# BatteryProtection.net
KiCad netlist of a schematic drawn in Altium Designer
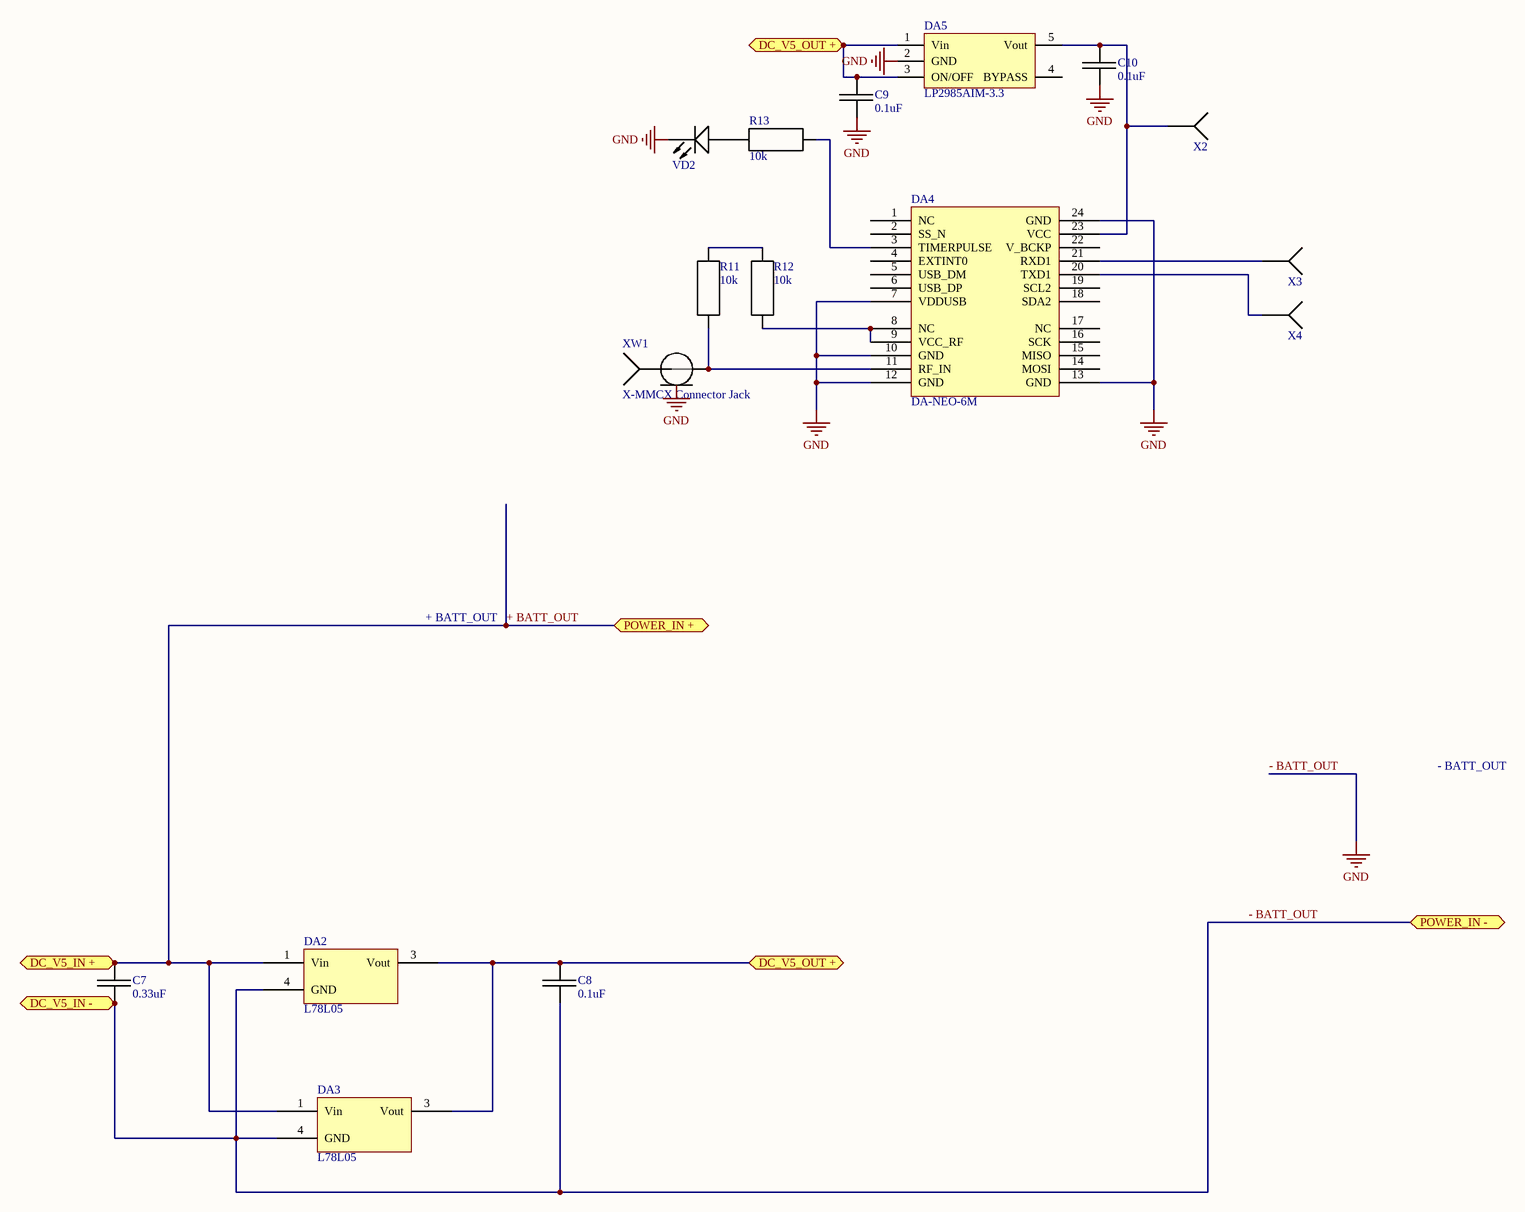
[diagram p0: BatteryProtection.SchDoc]

(export (version "E")
  (design (tool "Eeschema 10.0.6"))
  (components
    (comp (ref "C7")
      (value "0.33uF")
      (footprint "CAP0805")
      (fields (field (name "VOLTAGE") "50V"))
      (libsource (lib "Schlib1") (part "Capacitor"))
    )
    (comp (ref "C8")
      (value "0.1uF")
      (footprint "CAP0805")
      (fields (field (name "VOLTAGE") "50V"))
      (libsource (lib "Schlib1") (part "Capacitor"))
    )
    (comp (ref "C9")
      (value "0.1uF")
      (footprint "CAP0805")
      (fields (field (name "VOLTAGE") "50V"))
      (libsource (lib "Schlib1") (part "Capacitor"))
    )
    (comp (ref "C10")
      (value "0.1uF")
      (footprint "CAP0805")
      (fields (field (name "VOLTAGE") "50V"))
      (libsource (lib "Schlib1") (part "Capacitor"))
    )
    (comp (ref "DA2")
      (value "L78L05")
      (footprint "TO-252AA")
      (description "LDO")
      (libsource (lib "Schlib1") (part "DA-L78M05"))
    )
    (comp (ref "DA3")
      (value "L78L05")
      (footprint "TO-252AA")
      (description "LDO")
      (libsource (lib "Schlib1") (part "DA-L78M05"))
    )
    (comp (ref "DA4") (value "DA-NEO-6M") (footprint "NEO-6M") (libsource (lib "Schlib1") (part "DA-NEO-6M")))
    (comp (ref "DA5")
      (value "LP2985AIM-3.3")
      (footprint "SOT-23")
      (description "LDO")
      (libsource (lib "Schlib1") (part "DA-LP2985"))
    )
    (comp (ref "R11") (value "10k") (footprint "RES0805") (libsource (lib "") (part "Resistor_1")))
    (comp (ref "R12") (value "10k") (footprint "RES0805") (libsource (lib "") (part "Resistor_1")))
    (comp (ref "R13") (value "10k") (footprint "RES0805") (libsource (lib "Schlib1") (part "Resistor")))
    (comp (ref "VD2")
      (value "KP-1608SURC")
      (footprint "Diode 1608")
      (libsource (lib "Schlib1") (part "LED_0603"))
    )
    (comp (ref "X2") (value "X-Socket") (footprint "Socket") (libsource (lib "Schlib1") (part "X-Socket")))
    (comp (ref "X3") (value "X-Socket") (footprint "Socket") (libsource (lib "Schlib1") (part "X-Socket")))
    (comp (ref "X4") (value "X-Socket") (footprint "Socket") (libsource (lib "Schlib1") (part "X-Socket")))
    (comp (ref "XW1")
      (value "X-MMCX Connector Jack")
      (footprint "X-MMCX")
      (libsource (lib "Schlib1") (part "X-MMCX Connector Jack"))
    )
  )
  (nets
    (net (code "1") (name "/+ BATT_OUT") (class "Default")
      (node (ref "C7") (pin "1") (pinfunction "1_1") (pintype "passive"))
      (node (ref "DA2") (pin "1") (pinfunction "Vin_1") (pintype "passive"))
      (node (ref "DA3") (pin "1") (pinfunction "Vin_1") (pintype "passive"))
    )
    (net (code "2") (name "/DC_V5_OUT +") (class "Default")
      (node (ref "C8") (pin "1") (pinfunction "1_1") (pintype "passive"))
      (node (ref "C9") (pin "1") (pinfunction "1_1") (pintype "passive"))
      (node (ref "DA2") (pin "3") (pinfunction "Vout_3") (pintype "passive"))
      (node (ref "DA3") (pin "3") (pinfunction "Vout_3") (pintype "passive"))
      (node (ref "DA5") (pin "1") (pinfunction "Vin_1") (pintype "passive"))
      (node (ref "DA5") (pin "3") (pinfunction "ON/OFF_3") (pintype "passive"))
    )
    (net (code "3") (name "GND") (class "Default")
      (node (ref "C10") (pin "2") (pinfunction "2_2") (pintype "passive"))
      (node (ref "C7") (pin "2") (pinfunction "2_2") (pintype "passive"))
      (node (ref "C8") (pin "2") (pinfunction "2_2") (pintype "passive"))
      (node (ref "C9") (pin "2") (pinfunction "2_2") (pintype "passive"))
      (node (ref "DA2") (pin "4") (pinfunction "GND_4") (pintype "passive"))
      (node (ref "DA3") (pin "4") (pinfunction "GND_4") (pintype "passive"))
      (node (ref "DA4") (pin "10") (pinfunction "GND_10") (pintype "passive"))
      (node (ref "DA4") (pin "12") (pinfunction "GND_12") (pintype "passive"))
      (node (ref "DA4") (pin "13") (pinfunction "GND_13") (pintype "passive"))
      (node (ref "DA4") (pin "24") (pinfunction "GND_24") (pintype "passive"))
      (node (ref "DA4") (pin "7") (pinfunction "VDDUSB_7") (pintype "passive"))
      (node (ref "DA5") (pin "2") (pinfunction "GND_2") (pintype "passive"))
      (node (ref "VD2") (pin "1") (pinfunction "1_1") (pintype "passive"))
      (node (ref "XW1") (pin "2") (pinfunction "2_2") (pintype "passive"))
    )
    (net (code "4") (name "Net-(DA4-RF_IN)") (class "Default")
      (node (ref "DA4") (pin "11") (pinfunction "RF_IN_11") (pintype "passive"))
      (node (ref "R11") (pin "2") (pinfunction "2_2") (pintype "passive"))
      (node (ref "XW1") (pin "1") (pinfunction "1_1") (pintype "passive"))
    )
    (net (code "5") (name "Net-(DA4-RXD1)") (class "Default")
      (node (ref "DA4") (pin "21") (pinfunction "RXD1_21") (pintype "passive"))
      (node (ref "X3") (pin "1") (pinfunction "1_1") (pintype "passive"))
    )
    (net (code "6") (name "Net-(DA4-TIMERPULSE)") (class "Default")
      (node (ref "DA4") (pin "3") (pinfunction "TIMERPULSE_3") (pintype "passive"))
      (node (ref "R13") (pin "2") (pinfunction "2_2") (pintype "passive"))
    )
    (net (code "7") (name "Net-(DA4-TXD1)") (class "Default")
      (node (ref "DA4") (pin "20") (pinfunction "TXD1_20") (pintype "passive"))
      (node (ref "X4") (pin "1") (pinfunction "1_1") (pintype "passive"))
    )
    (net (code "8") (name "Net-(DA4-VCC)") (class "Default")
      (node (ref "C10") (pin "1") (pinfunction "1_1") (pintype "passive"))
      (node (ref "DA4") (pin "23") (pinfunction "VCC_23") (pintype "passive"))
      (node (ref "DA5") (pin "5") (pinfunction "Vout_5") (pintype "passive"))
      (node (ref "X2") (pin "1") (pinfunction "1_1") (pintype "passive"))
    )
    (net (code "9") (name "Net-(DA4-VCC_RF)") (class "Default")
      (node (ref "DA4") (pin "8") (pinfunction "NC_8") (pintype "passive"))
      (node (ref "DA4") (pin "9") (pinfunction "VCC_RF_9") (pintype "passive"))
      (node (ref "R12") (pin "2") (pinfunction "2_2") (pintype "passive"))
    )
    (net (code "10") (name "Net-(R11-Pad1)") (class "Default")
      (node (ref "R11") (pin "1") (pinfunction "1_1") (pintype "passive"))
      (node (ref "R12") (pin "1") (pinfunction "1_1") (pintype "passive"))
    )
    (net (code "11") (name "Net-(R13-Pad1)") (class "Default")
      (node (ref "R13") (pin "1") (pinfunction "1_1") (pintype "passive"))
      (node (ref "VD2") (pin "2") (pinfunction "2_2") (pintype "passive"))
    )
    (net (code "12") (name "unconnected-(DA4-EXTINT0-Pad4)") (class "Default")
      (node (ref "DA4") (pin "4") (pinfunction "EXTINT0_4") (pintype "passive"))
    )
    (net (code "13") (name "unconnected-(DA4-MISO-Pad15)") (class "Default")
      (node (ref "DA4") (pin "15") (pinfunction "MISO_15") (pintype "passive"))
    )
    (net (code "14") (name "unconnected-(DA4-MOSI-Pad14)") (class "Default")
      (node (ref "DA4") (pin "14") (pinfunction "MOSI_14") (pintype "passive"))
    )
    (net (code "15") (name "unconnected-(DA4-NC-Pad1)") (class "Default")
      (node (ref "DA4") (pin "1") (pinfunction "NC_1") (pintype "passive"))
    )
    (net (code "16") (name "unconnected-(DA4-NC-Pad17)") (class "Default")
      (node (ref "DA4") (pin "17") (pinfunction "NC_17") (pintype "passive"))
    )
    (net (code "17") (name "unconnected-(DA4-SCK-Pad16)") (class "Default")
      (node (ref "DA4") (pin "16") (pinfunction "SCK_16") (pintype "passive"))
    )
    (net (code "18") (name "unconnected-(DA4-SCL2-Pad19)") (class "Default")
      (node (ref "DA4") (pin "19") (pinfunction "SCL2_19") (pintype "passive"))
    )
    (net (code "19") (name "unconnected-(DA4-SDA2-Pad18)") (class "Default")
      (node (ref "DA4") (pin "18") (pinfunction "SDA2_18") (pintype "passive"))
    )
    (net (code "20") (name "unconnected-(DA4-SS_N-Pad2)") (class "Default")
      (node (ref "DA4") (pin "2") (pinfunction "SS_N_2") (pintype "passive"))
    )
    (net (code "21") (name "unconnected-(DA4-USB_DM-Pad5)") (class "Default")
      (node (ref "DA4") (pin "5") (pinfunction "USB_DM_5") (pintype "passive"))
    )
    (net (code "22") (name "unconnected-(DA4-USB_DP-Pad6)") (class "Default")
      (node (ref "DA4") (pin "6") (pinfunction "USB_DP_6") (pintype "passive"))
    )
    (net (code "23") (name "unconnected-(DA4-V_BCKP-Pad22)") (class "Default")
      (node (ref "DA4") (pin "22") (pinfunction "V_BCKP_22") (pintype "passive"))
    )
    (net (code "24") (name "unconnected-(DA5-BYPASS-Pad4)") (class "Default")
      (node (ref "DA5") (pin "4") (pinfunction "BYPASS_4") (pintype "passive"))
    )
  )
)
